# CSS811_BME280_Breakout.net
KiCad netlist of a schematic drawn in EAGLE
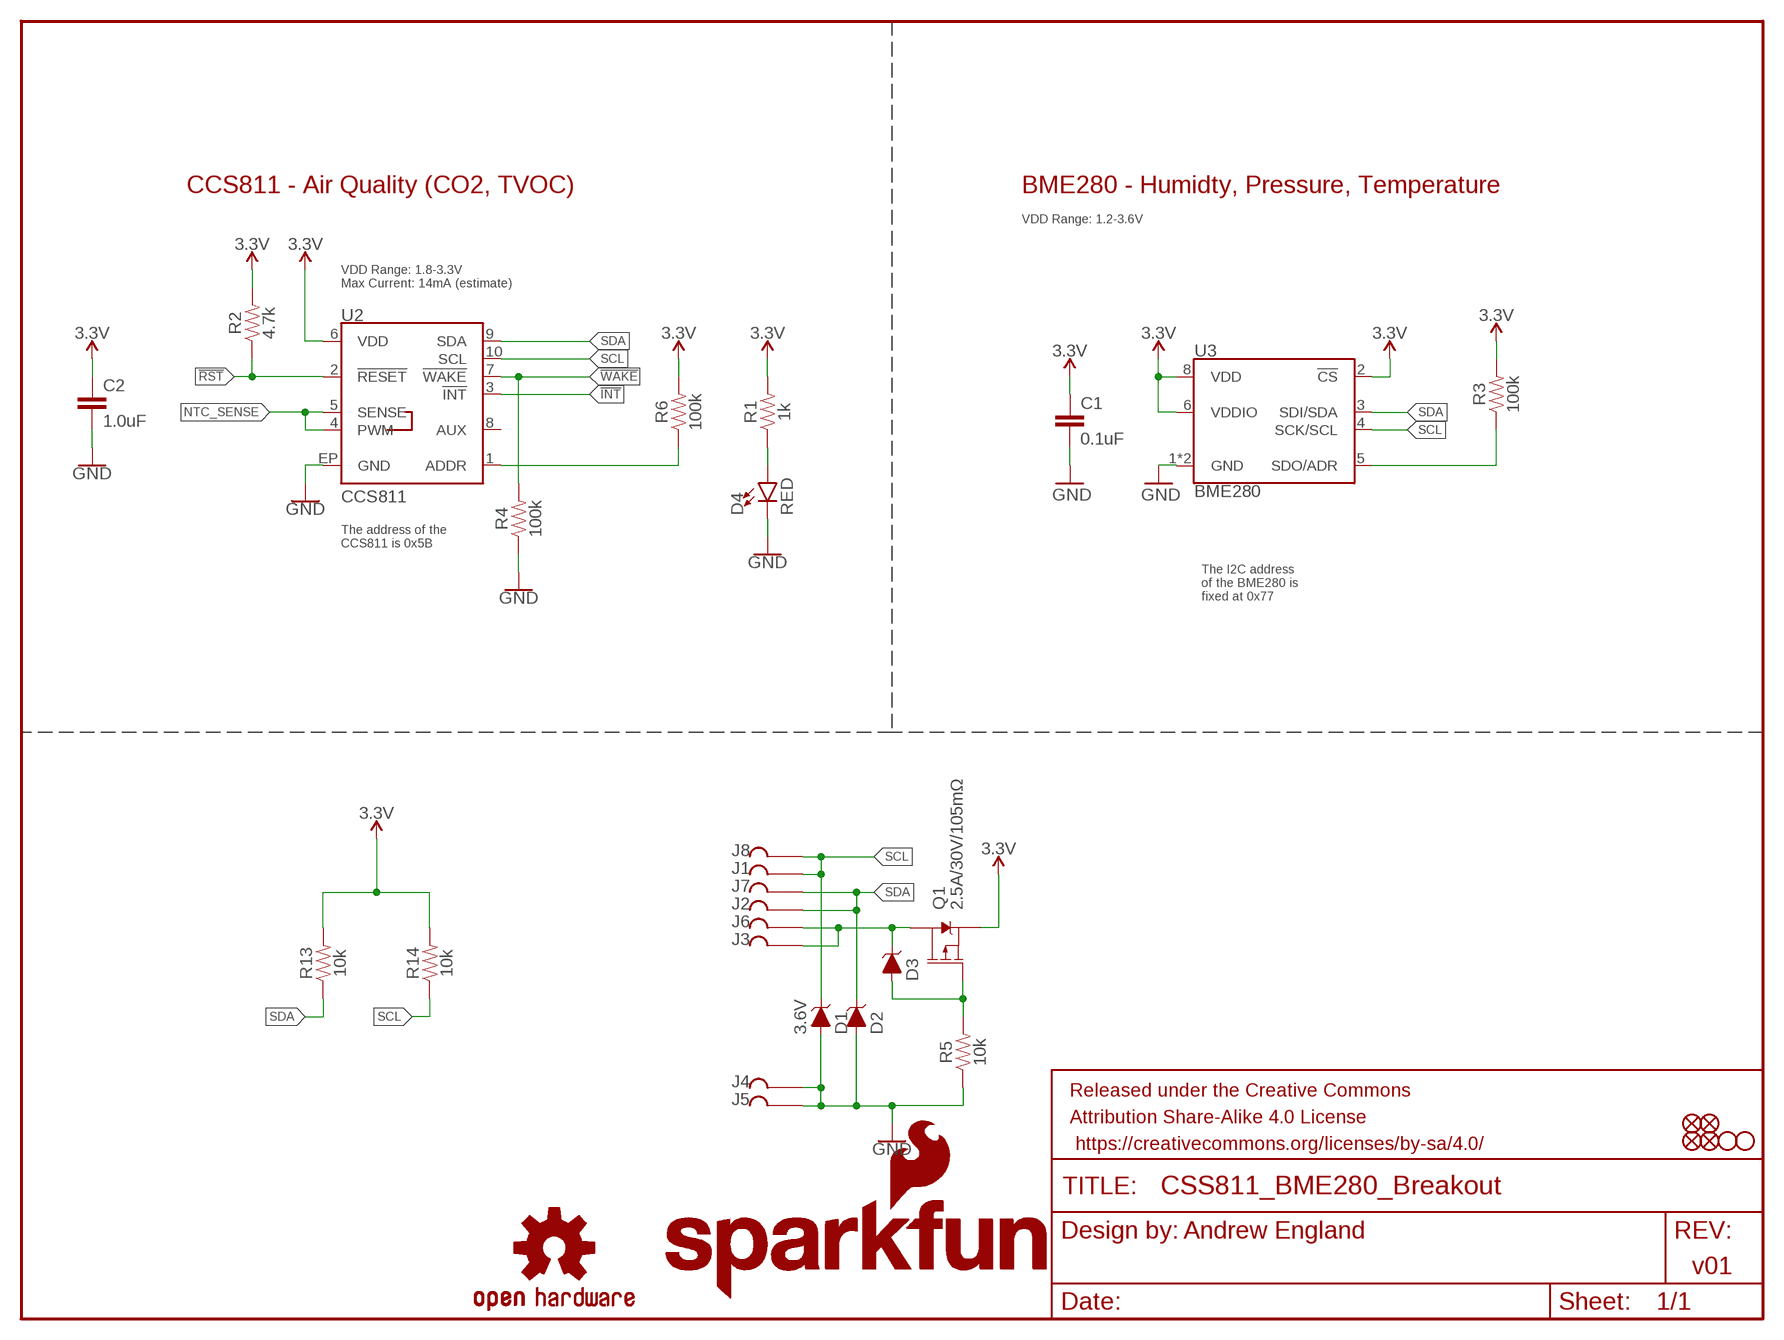
[diagram p0: schematic, sheet 1]

(export (version "E")
  (design (tool "Eeschema 10.0.6"))
  (components
    (comp (ref "C1")
      (value "0.1uF")
      (footprint "eagle-import:0603")
      (libsource (lib "eagle-import") (part "0.1UF-0603-25V-(+80/-20%)"))
    )
    (comp (ref "C2")
      (value "1.0uF")
      (footprint "eagle-import:0603")
      (libsource (lib "eagle-import") (part "1.0UF-0603-16V-10%"))
    )
    (comp (ref "D1")
      (value "3.6V")
      (footprint "eagle-import:SOD-323")
      (libsource (lib "eagle-import") (part "DIODE-ZENER-BZT52C3V6S"))
    )
    (comp (ref "D2")
      (value "3.6V")
      (footprint "eagle-import:SOD-323")
      (libsource (lib "eagle-import") (part "DIODE-ZENER-BZT52C3V6S"))
    )
    (comp (ref "D3")
      (value "3.6V")
      (footprint "eagle-import:SOD-323")
      (libsource (lib "eagle-import") (part "DIODE-ZENER-BZT52C3V6S"))
    )
    (comp (ref "D4")
      (value "RED")
      (footprint "eagle-import:LED-0603")
      (libsource (lib "eagle-import") (part "LED-RED0603"))
    )
    (comp (ref "FD1")
      (value "FIDUCIAL1X2")
      (footprint "eagle-import:FIDUCIAL-1X2")
      (libsource (lib "eagle-import") (part "FIDUCIAL1X2"))
    )
    (comp (ref "FD2")
      (value "FIDUCIAL1X2")
      (footprint "eagle-import:FIDUCIAL-1X2")
      (libsource (lib "eagle-import") (part "FIDUCIAL1X2"))
    )
    (comp (ref "FD3")
      (value "FIDUCIAL1X2")
      (footprint "eagle-import:FIDUCIAL-1X2")
      (libsource (lib "eagle-import") (part "FIDUCIAL1X2"))
    )
    (comp (ref "FD4")
      (value "FIDUCIAL1X2")
      (footprint "eagle-import:FIDUCIAL-1X2")
      (libsource (lib "eagle-import") (part "FIDUCIAL1X2"))
    )
    (comp (ref "FRAME1")
      (value "FRAME-LETTER")
      (footprint "eagle-import:CREATIVE_COMMONS")
      (libsource (lib "eagle-import") (part "FRAME-LETTER"))
    )
    (comp (ref "H2")
      (value "STAND-OFF")
      (footprint "eagle-import:STAND-OFF")
      (libsource (lib "eagle-import") (part "STAND-OFF"))
    )
    (comp (ref "H4")
      (value "STAND-OFF")
      (footprint "eagle-import:STAND-OFF")
      (libsource (lib "eagle-import") (part "STAND-OFF"))
    )
    (comp (ref "J1")
      (value "GATORGATOR_MINI")
      (footprint "eagle-import:GATOR_MINI")
      (libsource (lib "eagle-import") (part "GATORGATOR_MINI"))
    )
    (comp (ref "J2")
      (value "GATORGATOR_MINI")
      (footprint "eagle-import:GATOR_MINI")
      (libsource (lib "eagle-import") (part "GATORGATOR_MINI"))
    )
    (comp (ref "J3")
      (value "GATORGATOR_MINI")
      (footprint "eagle-import:GATOR_MINI")
      (libsource (lib "eagle-import") (part "GATORGATOR_MINI"))
    )
    (comp (ref "J4")
      (value "GATORGATOR_MINI")
      (footprint "eagle-import:GATOR_MINI")
      (libsource (lib "eagle-import") (part "GATORGATOR_MINI"))
    )
    (comp (ref "J5")
      (value "GATORGATOR_MINI")
      (footprint "eagle-import:GATOR_MINI")
      (libsource (lib "eagle-import") (part "GATORGATOR_MINI"))
    )
    (comp (ref "J6")
      (value "GATORGATOR_MINI")
      (footprint "eagle-import:GATOR_MINI")
      (libsource (lib "eagle-import") (part "GATORGATOR_MINI"))
    )
    (comp (ref "J7")
      (value "GATORGATOR_MINI")
      (footprint "eagle-import:GATOR_MINI")
      (libsource (lib "eagle-import") (part "GATORGATOR_MINI"))
    )
    (comp (ref "J8")
      (value "GATORGATOR_MINI")
      (footprint "eagle-import:GATOR_MINI")
      (libsource (lib "eagle-import") (part "GATORGATOR_MINI"))
    )
    (comp (ref "LOGO1")
      (value "SFE_LOGO_NAME.1_INCH")
      (footprint "eagle-import:SFE_LOGO_NAME_.1")
      (libsource (lib "eagle-import") (part "SFE_LOGO_NAME.1_INCH"))
    )
    (comp (ref "LOGO2")
      (value "SFE_LOGO_NAME_FLAME.1_INCH")
      (footprint "eagle-import:SFE_LOGO_NAME_FLAME_.1")
      (libsource (lib "eagle-import") (part "SFE_LOGO_NAME_FLAME.1_INCH"))
    )
    (comp (ref "LOGO4")
      (value "OSHW-LOGOS")
      (footprint "eagle-import:OSHW-LOGO-S")
      (libsource (lib "eagle-import") (part "OSHW-LOGOS"))
    )
    (comp (ref "Q1")
      (value "2.5A/30V/105mΩ")
      (footprint "eagle-import:SOT23-3")
      (libsource (lib "eagle-import") (part "MOSFET_PCH-DMG2307L"))
    )
    (comp (ref "R1")
      (value "1k")
      (footprint "eagle-import:0603")
      (libsource (lib "eagle-import") (part "1KOHM-0603-1/10W-1%"))
    )
    (comp (ref "R2")
      (value "4.7k")
      (footprint "eagle-import:0603")
      (libsource (lib "eagle-import") (part "4.7KOHM-0603-1/10W-1%"))
    )
    (comp (ref "R3")
      (value "100k")
      (footprint "eagle-import:0603")
      (libsource (lib "eagle-import") (part "100KOHM-0603-1/10W-1%"))
    )
    (comp (ref "R4")
      (value "100k")
      (footprint "eagle-import:0603")
      (libsource (lib "eagle-import") (part "100KOHM-0603-1/10W-1%"))
    )
    (comp (ref "R5")
      (value "10k")
      (footprint "eagle-import:0603")
      (libsource (lib "eagle-import") (part "10KOHM-0603-1/10W-1%"))
    )
    (comp (ref "R6")
      (value "100k")
      (footprint "eagle-import:0603")
      (libsource (lib "eagle-import") (part "100KOHM-0603-1/10W-1%"))
    )
    (comp (ref "R13")
      (value "10k")
      (footprint "eagle-import:0603")
      (libsource (lib "eagle-import") (part "10KOHM-0603-1/10W-1%"))
    )
    (comp (ref "R14")
      (value "10k")
      (footprint "eagle-import:0603")
      (libsource (lib "eagle-import") (part "10KOHM-0603-1/10W-1%"))
    )
    (comp (ref "U2")
      (value "CCS811")
      (footprint "eagle-import:LGA10")
      (libsource (lib "eagle-import") (part "CCS811PRODUCTION"))
    )
    (comp (ref "U3")
      (value "BME280")
      (footprint "eagle-import:LGA-8-2.5X2.5")
      (libsource (lib "eagle-import") (part "BME280"))
    )
  )
  (nets
    (net (code "1") (name "/~{INT}") (class "Default")
      (node (ref "U2") (pin "3") (pinfunction "~{INT}_3") (pintype "bidirectional"))
    )
    (net (code "2") (name "/~{RST}") (class "Default")
      (node (ref "R2") (pin "1") (pinfunction "1_1") (pintype "passive"))
      (node (ref "U2") (pin "2") (pinfunction "~{RESET}_2") (pintype "bidirectional"))
    )
    (net (code "3") (name "/~{WAKE}") (class "Default")
      (node (ref "R4") (pin "2") (pinfunction "2_2") (pintype "passive"))
      (node (ref "U2") (pin "7") (pinfunction "~{WAKE}_7") (pintype "bidirectional"))
    )
    (net (code "4") (name "3.3V") (class "Default")
      (node (ref "C1") (pin "1") (pinfunction "1_1") (pintype "passive"))
      (node (ref "C2") (pin "1") (pinfunction "1_1") (pintype "passive"))
      (node (ref "Q1") (pin "2") (pinfunction "S_2") (pintype "bidirectional"))
      (node (ref "R1") (pin "2") (pinfunction "2_2") (pintype "passive"))
      (node (ref "R13") (pin "2") (pinfunction "2_2") (pintype "passive"))
      (node (ref "R14") (pin "2") (pinfunction "2_2") (pintype "passive"))
      (node (ref "R2") (pin "2") (pinfunction "2_2") (pintype "passive"))
      (node (ref "R3") (pin "2") (pinfunction "2_2") (pintype "passive"))
      (node (ref "R6") (pin "2") (pinfunction "2_2") (pintype "passive"))
      (node (ref "U2") (pin "6") (pinfunction "VDD_6") (pintype "bidirectional"))
      (node (ref "U3") (pin "2") (pinfunction "~{CS}_2") (pintype "bidirectional"))
      (node (ref "U3") (pin "6") (pinfunction "VDDIO_6") (pintype "bidirectional"))
      (node (ref "U3") (pin "8") (pinfunction "VDD_8") (pintype "bidirectional"))
    )
    (net (code "5") (name "GND") (class "Default")
      (node (ref "C1") (pin "2") (pinfunction "2_2") (pintype "passive"))
      (node (ref "C2") (pin "2") (pinfunction "2_2") (pintype "passive"))
      (node (ref "D1") (pin "A") (pinfunction "A_A") (pintype "passive"))
      (node (ref "D2") (pin "A") (pinfunction "A_A") (pintype "passive"))
      (node (ref "D4") (pin "C") (pinfunction "C_C") (pintype "passive"))
      (node (ref "J4") (pin "P$2") (pinfunction "P$1_P$2") (pintype "bidirectional"))
      (node (ref "J5") (pin "P$2") (pinfunction "P$1_P$2") (pintype "bidirectional"))
      (node (ref "R4") (pin "1") (pinfunction "1_1") (pintype "passive"))
      (node (ref "R5") (pin "1") (pinfunction "1_1") (pintype "passive"))
      (node (ref "U2") (pin "EP") (pinfunction "GND_EP") (pintype "bidirectional"))
      (node (ref "U3") (pin "1") (pinfunction "GND_1") (pintype "bidirectional"))
      (node (ref "U3") (pin "7") (pinfunction "GND_7") (pintype "bidirectional"))
    )
    (net (code "6") (name "NTC_SENSE") (class "Default")
      (node (ref "U2") (pin "4") (pinfunction "PWM_4") (pintype "bidirectional"))
      (node (ref "U2") (pin "5") (pinfunction "SENSE_5") (pintype "bidirectional"))
    )
    (net (code "7") (name "Net-(D4-PadA)") (class "Default")
      (node (ref "D4") (pin "A") (pinfunction "A_A") (pintype "passive"))
      (node (ref "R1") (pin "1") (pinfunction "1_1") (pintype "passive"))
    )
    (net (code "8") (name "Net-(J3-P$1)") (class "Default")
      (node (ref "D3") (pin "C") (pinfunction "C_C") (pintype "passive"))
      (node (ref "J3") (pin "P$2") (pinfunction "P$1_P$2") (pintype "bidirectional"))
      (node (ref "J6") (pin "P$2") (pinfunction "P$1_P$2") (pintype "bidirectional"))
      (node (ref "Q1") (pin "3") (pinfunction "D_3") (pintype "bidirectional"))
    )
    (net (code "9") (name "Net-(Q1-G)") (class "Default")
      (node (ref "D3") (pin "A") (pinfunction "A_A") (pintype "passive"))
      (node (ref "Q1") (pin "1") (pinfunction "G_1") (pintype "bidirectional"))
      (node (ref "R5") (pin "2") (pinfunction "2_2") (pintype "passive"))
    )
    (net (code "10") (name "Net-(U2-ADDR)") (class "Default")
      (node (ref "R6") (pin "1") (pinfunction "1_1") (pintype "passive"))
      (node (ref "U2") (pin "1") (pinfunction "ADDR_1") (pintype "bidirectional"))
    )
    (net (code "11") (name "Net-(U3-SDO{slash}ADR)") (class "Default")
      (node (ref "R3") (pin "1") (pinfunction "1_1") (pintype "passive"))
      (node (ref "U3") (pin "5") (pinfunction "SDO/ADR_5") (pintype "bidirectional"))
    )
    (net (code "12") (name "SCL") (class "Default")
      (node (ref "D1") (pin "C") (pinfunction "C_C") (pintype "passive"))
      (node (ref "J1") (pin "P$2") (pinfunction "P$1_P$2") (pintype "bidirectional"))
      (node (ref "J8") (pin "P$2") (pinfunction "P$1_P$2") (pintype "bidirectional"))
      (node (ref "R14") (pin "1") (pinfunction "1_1") (pintype "passive"))
      (node (ref "U2") (pin "10") (pinfunction "SCL_10") (pintype "bidirectional"))
      (node (ref "U3") (pin "4") (pinfunction "SCK/SCL_4") (pintype "bidirectional"))
    )
    (net (code "13") (name "SDA") (class "Default")
      (node (ref "D2") (pin "C") (pinfunction "C_C") (pintype "passive"))
      (node (ref "J2") (pin "P$2") (pinfunction "P$1_P$2") (pintype "bidirectional"))
      (node (ref "J7") (pin "P$2") (pinfunction "P$1_P$2") (pintype "bidirectional"))
      (node (ref "R13") (pin "1") (pinfunction "1_1") (pintype "passive"))
      (node (ref "U2") (pin "9") (pinfunction "SDA_9") (pintype "bidirectional"))
      (node (ref "U3") (pin "3") (pinfunction "SDI/SDA_3") (pintype "bidirectional"))
    )
    (net (code "14") (name "unconnected-(U2-AUX-Pad8)") (class "Default")
      (node (ref "U2") (pin "8") (pinfunction "AUX_8") (pintype "bidirectional"))
    )
  )
)
